# Low_power_detector.net
KiCad netlist of a schematic drawn in Altium Designer
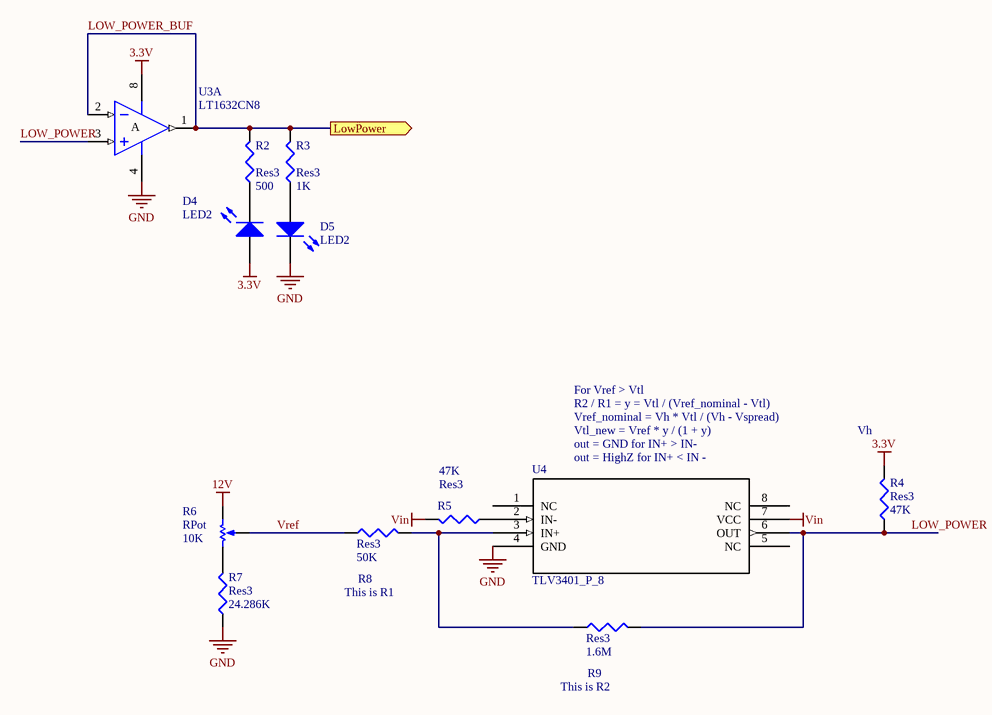
[diagram p0: Low_power_detector.SchDoc]

(export (version "E")
  (design (tool "Eeschema 10.0.6"))
  (components
    (comp (ref "D4")
      (value "LED2")
      (footprint "3.2X1.6X1.1")
      (description "Typical RED, GREEN, YELLOW, AMBER GaAs LED")
      (fields (field (name "PUBLISHER") "Altium Limited"))
      (libsource (lib "Miscellaneous Devices") (part "LED2"))
    )
    (comp (ref "D5")
      (value "LED2")
      (footprint "3.2X1.6X1.1")
      (description "Typical RED, GREEN, YELLOW, AMBER GaAs LED")
      (fields (field (name "PUBLISHER") "Altium Limited"))
      (libsource (lib "Miscellaneous Devices") (part "LED2"))
    )
    (comp (ref "R2")
      (value "Res3")
      (footprint "AXIAL-0.3")
      (description "Resistor")
      (fields (field (name "ALTIUM_VALUE") "500") (field (name "PUBLISHER") "Altium Limited"))
      (libsource (lib "Miscellaneous Devices") (part "Res3"))
    )
    (comp (ref "R3")
      (value "Res3")
      (footprint "AXIAL-0.3")
      (description "Resistor")
      (fields (field (name "ALTIUM_VALUE") "1K") (field (name "PUBLISHER") "Altium Limited"))
      (libsource (lib "Miscellaneous Devices") (part "Res3"))
    )
    (comp (ref "R4")
      (value "Res3")
      (footprint "AXIAL-0.3")
      (description "Resistor")
      (fields (field (name "ALTIUM_VALUE") "47K") (field (name "PUBLISHER") "Altium Limited"))
      (libsource (lib "Miscellaneous Devices") (part "Res3"))
    )
    (comp (ref "R5")
      (value "Res3")
      (footprint "AXIAL-0.3")
      (description "Resistor")
      (fields (field (name "ALTIUM_VALUE") "47K") (field (name "PUBLISHER") "Altium Limited"))
      (libsource (lib "Miscellaneous Devices") (part "Res3"))
    )
    (comp (ref "R6")
      (value "RPot")
      (footprint "RPot")
      (description "Potentiometer")
      (fields (field (name "ALTIUM_VALUE") "10K") (field (name "PUBLISHER") "Altium Limited"))
      (libsource (lib "Miscellaneous Devices") (part "RPot"))
    )
    (comp (ref "R7")
      (value "Res3")
      (footprint "AXIAL-0.3")
      (description "Resistor")
      (fields (field (name "ALTIUM_VALUE") "24.286K") (field (name "PUBLISHER") "Altium Limited"))
      (libsource (lib "Miscellaneous Devices") (part "Res3"))
    )
    (comp (ref "R8")
      (value "Res3")
      (footprint "AXIAL-0.3")
      (description "Resistor")
      (fields (field (name "ALTIUM_VALUE") "50K") (field (name "PUBLISHER") "Altium Limited"))
      (libsource (lib "Miscellaneous Devices") (part "Res3"))
    )
    (comp (ref "R9")
      (value "Res3")
      (footprint "AXIAL-0.3")
      (description "Resistor")
      (fields (field (name "ALTIUM_VALUE") "1.6M") (field (name "PUBLISHER") "Altium Limited"))
      (libsource (lib "Miscellaneous Devices") (part "Res3"))
    )
    (comp (ref "U3")
      (value "LT1632CN8")
      (footprint "P8")
      (description "45MHz, 45V/µs, Dual Rail-to-Rail Input and Output Precision Operational Amplifier")
      (fields (field (name "PUBLISHER") "Altium Limited"))
      (libsource (lib "ECE Lib (1)") (part "LT1632CN8"))
    )
    (comp (ref "U4")
      (value "TLV3401_P_8")
      (footprint "P8")
      (description "Imported")
      (fields
        (field (name "MANUFACTURER_PART_NUMBER") "tlv3401_p_8")
        (field (name "GENERIC_PART_NUMBER") "TLV3401")
      )
      (libsource (lib "TLV3401P") (part "TLV3401_P_8"))
    )
  )
  (nets
    (net (code "1") (name "/LOW_POWER") (class "Default")
      (node (ref "R4") (pin "1") (pinfunction "1_1") (pintype "passive"))
      (node (ref "R9") (pin "2") (pinfunction "2_2") (pintype "passive"))
      (node (ref "U3") (pin "3") (pinfunction "IN+_3") (pintype "input"))
      (node (ref "U4") (pin "6") (pinfunction "OUT_6") (pintype "output"))
    )
    (net (code "2") (name "/LOW_POWER_BUF") (class "Default")
      (node (ref "R2") (pin "2") (pinfunction "2_2") (pintype "passive"))
      (node (ref "R3") (pin "2") (pinfunction "2_2") (pintype "passive"))
      (node (ref "U3") (pin "1") (pinfunction "OUT_1") (pintype "output"))
      (node (ref "U3") (pin "2") (pinfunction "IN-_2") (pintype "input"))
    )
    (net (code "3") (name "/Vref") (class "Default")
      (node (ref "R6") (pin "3") (pinfunction "TAP_3") (pintype "passive"))
      (node (ref "R8") (pin "1") (pinfunction "1_1") (pintype "passive"))
    )
    (net (code "4") (name "3.3V") (class "Default")
      (node (ref "D4") (pin "1") (pinfunction "A_1") (pintype "passive"))
      (node (ref "R4") (pin "2") (pinfunction "2_2") (pintype "passive"))
      (node (ref "U3") (pin "8") (pinfunction "V+_8") (pintype "power_in"))
    )
    (net (code "5") (name "12V") (class "Default")
      (node (ref "R6") (pin "1") (pinfunction "TOP_1") (pintype "passive"))
    )
    (net (code "6") (name "GND") (class "Default")
      (node (ref "D5") (pin "2") (pinfunction "K_2") (pintype "passive"))
      (node (ref "R7") (pin "1") (pinfunction "1_1") (pintype "passive"))
      (node (ref "U3") (pin "4") (pinfunction "V-_4") (pintype "power_in"))
      (node (ref "U4") (pin "4") (pinfunction "GND_4") (pintype "power_in"))
    )
    (net (code "7") (name "Net-(D4-K)") (class "Default")
      (node (ref "D4") (pin "2") (pinfunction "K_2") (pintype "passive"))
      (node (ref "R2") (pin "1") (pinfunction "1_1") (pintype "passive"))
    )
    (net (code "8") (name "Net-(D5-A)") (class "Default")
      (node (ref "D5") (pin "1") (pinfunction "A_1") (pintype "passive"))
      (node (ref "R3") (pin "1") (pinfunction "1_1") (pintype "passive"))
    )
    (net (code "9") (name "Net-(R6-BOT)") (class "Default")
      (node (ref "R6") (pin "2") (pinfunction "BOT_2") (pintype "passive"))
      (node (ref "R7") (pin "2") (pinfunction "2_2") (pintype "passive"))
    )
    (net (code "10") (name "Net-(U4-IN+)") (class "Default")
      (node (ref "R8") (pin "2") (pinfunction "2_2") (pintype "passive"))
      (node (ref "R9") (pin "1") (pinfunction "1_1") (pintype "passive"))
      (node (ref "U4") (pin "3") (pinfunction "IN+_3") (pintype "input"))
    )
    (net (code "11") (name "Net-(U4-IN-)") (class "Default")
      (node (ref "R5") (pin "1") (pinfunction "1_1") (pintype "passive"))
      (node (ref "U4") (pin "2") (pinfunction "IN-_2") (pintype "input"))
    )
    (net (code "12") (name "Vin") (class "Default")
      (node (ref "R5") (pin "2") (pinfunction "2_2") (pintype "passive"))
      (node (ref "U4") (pin "7") (pinfunction "VCC_7") (pintype "power_in"))
    )
    (net (code "13") (name "unconnected-(U4-NC-Pad1)") (class "Default")
      (node (ref "U4") (pin "1") (pinfunction "NC_1") (pintype "passive"))
    )
    (net (code "14") (name "unconnected-(U4-NC-Pad5)") (class "Default")
      (node (ref "U4") (pin "5") (pinfunction "NC_5") (pintype "passive"))
    )
    (net (code "15") (name "unconnected-(U4-NC-Pad8)") (class "Default")
      (node (ref "U4") (pin "8") (pinfunction "NC_8") (pintype "passive"))
    )
  )
)
